# Meter.net
KiCad netlist of a schematic drawn in Altium Designer
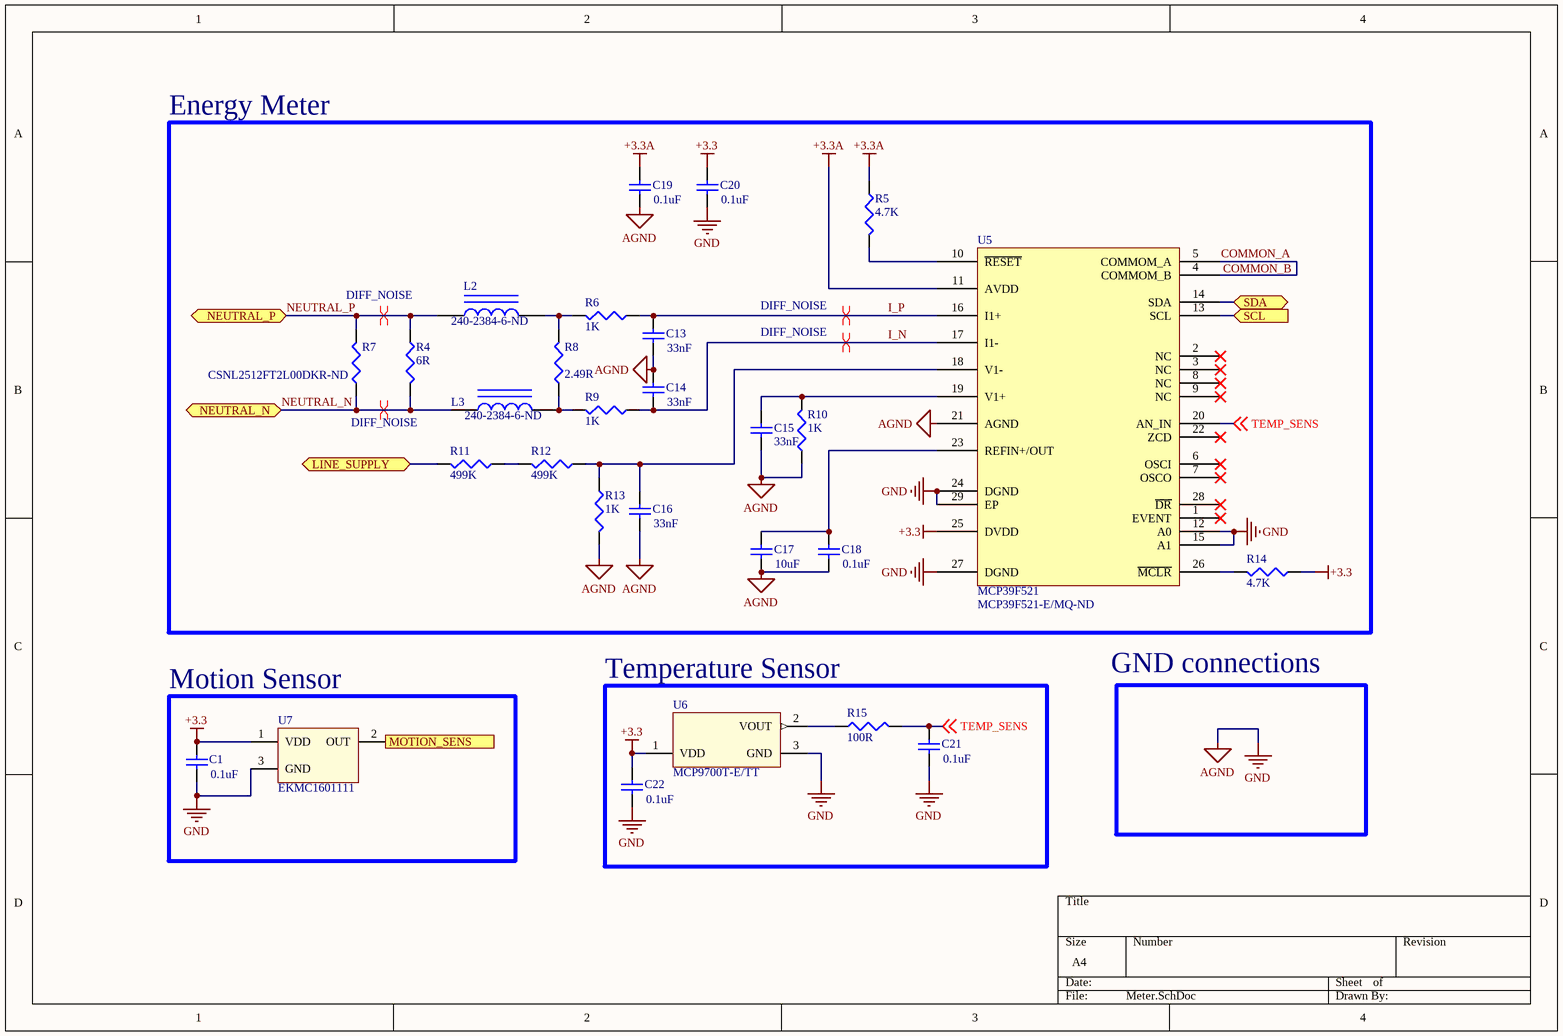
[diagram p0: Meter.SchDoc]

(export (version "E")
  (design (tool "Eeschema 10.0.6"))
  (components
    (comp (ref "C1")
      (value "0.1uF")
      (footprint "C0603")
      (description "Capacitor (Semiconductor SIM Model)")
      (fields (field (name "Comment") "MUDAR FOOTPRINT") (field (name "PUBLISHER") "Altium Limited"))
      (libsource (lib "Miscellaneous Devices") (part "Cap Semi"))
    )
    (comp (ref "C13")
      (value "33nF")
      (footprint "C0603")
      (description "Capacitor (Semiconductor SIM Model)")
      (fields (field (name "Comment") "MUDAR FOOTPRINT") (field (name "PUBLISHER") "Altium Limited"))
      (libsource (lib "Miscellaneous Devices") (part "Cap Semi"))
    )
    (comp (ref "C14")
      (value "33nF")
      (footprint "C0603")
      (description "Capacitor (Semiconductor SIM Model)")
      (fields (field (name "Comment") "MUDAR FOOTPRINT") (field (name "PUBLISHER") "Altium Limited"))
      (libsource (lib "Miscellaneous Devices") (part "Cap Semi"))
    )
    (comp (ref "C15")
      (value "33nF")
      (footprint "C0603")
      (description "Capacitor (Semiconductor SIM Model)")
      (fields (field (name "Comment") "MUDAR FOOTPRINT") (field (name "PUBLISHER") "Altium Limited"))
      (libsource (lib "Miscellaneous Devices") (part "Cap Semi"))
    )
    (comp (ref "C16")
      (value "33nF")
      (footprint "C0603")
      (description "Capacitor (Semiconductor SIM Model)")
      (fields (field (name "Comment") "MUDAR FOOTPRINT") (field (name "PUBLISHER") "Altium Limited"))
      (libsource (lib "Miscellaneous Devices") (part "Cap Semi"))
    )
    (comp (ref "C17")
      (value "10uF")
      (footprint "C0805")
      (description "Capacitor (Semiconductor SIM Model)")
      (fields (field (name "Comment") "MUDAR FOOTPRINT") (field (name "PUBLISHER") "Altium Limited"))
      (libsource (lib "Miscellaneous Devices") (part "Cap Semi"))
    )
    (comp (ref "C18")
      (value "0.1uF")
      (footprint "C0603")
      (description "Capacitor (Semiconductor SIM Model)")
      (fields (field (name "Comment") "MUDAR FOOTPRINT") (field (name "PUBLISHER") "Altium Limited"))
      (libsource (lib "Miscellaneous Devices") (part "Cap Semi"))
    )
    (comp (ref "C19")
      (value "0.1uF")
      (footprint "C0603")
      (description "Capacitor (Semiconductor SIM Model)")
      (fields (field (name "Comment") "MUDAR FOOTPRINT") (field (name "PUBLISHER") "Altium Limited"))
      (libsource (lib "Miscellaneous Devices") (part "Cap Semi"))
    )
    (comp (ref "C20")
      (value "0.1uF")
      (footprint "C0603")
      (description "Capacitor (Semiconductor SIM Model)")
      (fields (field (name "Comment") "MUDAR FOOTPRINT") (field (name "PUBLISHER") "Altium Limited"))
      (libsource (lib "Miscellaneous Devices") (part "Cap Semi"))
    )
    (comp (ref "C21")
      (value "0.1uF")
      (footprint "C0603")
      (description "Capacitor (Semiconductor SIM Model)")
      (fields (field (name "Comment") "MUDAR FOOTPRINT") (field (name "PUBLISHER") "Altium Limited"))
      (libsource (lib "Miscellaneous Devices") (part "Cap Semi"))
    )
    (comp (ref "C22")
      (value "0.1uF")
      (footprint "C0603")
      (description "Capacitor (Semiconductor SIM Model)")
      (fields (field (name "Comment") "MUDAR FOOTPRINT") (field (name "PUBLISHER") "Altium Limited"))
      (libsource (lib "Miscellaneous Devices") (part "Cap Semi"))
    )
    (comp (ref "L2")
      (value "FERRITE BEAD")
      (footprint "6-0805_N")
      (description "Magnetic-Core Inductor")
      (fields
        (field (name "SUPPLIER PART NUMBER 1") "240-2384-6-ND")
        (field (name "PUBLISHER") "Altium Limited")
      )
      (libsource (lib "Miscellaneous Devices") (part "Inductor Iron"))
    )
    (comp (ref "L3")
      (value "FERRITE BEAD")
      (footprint "6-0805_N")
      (description "Magnetic-Core Inductor")
      (fields
        (field (name "SUPPLIER PART NUMBER 1") "240-2384-6-ND")
        (field (name "PUBLISHER") "Altium Limited")
      )
      (libsource (lib "Miscellaneous Devices") (part "Inductor Iron"))
    )
    (comp (ref "R4")
      (value "6R")
      (footprint "R0603")
      (description "Resistor")
      (fields (field (name "Comment") "Res3") (field (name "PUBLISHER") "Altium Limited"))
      (libsource (lib "Miscellaneous Devices") (part "Res3"))
    )
    (comp (ref "R5")
      (value "4.7K")
      (footprint "R0603")
      (description "Resistor")
      (fields (field (name "Comment") "Res3") (field (name "PUBLISHER") "Altium Limited"))
      (libsource (lib "Miscellaneous Devices") (part "Res3"))
    )
    (comp (ref "R6")
      (value "1K")
      (footprint "R0603")
      (description "Resistor")
      (fields (field (name "Comment") "Res3") (field (name "PUBLISHER") "Altium Limited"))
      (libsource (lib "Miscellaneous Devices") (part "Res3"))
    )
    (comp (ref "R7")
      (value "SHUNT")
      (footprint "RES2512")
      (description "Resistor")
      (fields
        (field (name "SUPPLIER PART NUMBER 1") "CSNL2512FT2L00DKR-ND")
        (field (name "PUBLISHER") "Altium Limited")
      )
      (libsource (lib "Miscellaneous Devices") (part "Res3"))
    )
    (comp (ref "R8")
      (value "2.49R")
      (footprint "R0603")
      (description "Resistor")
      (fields (field (name "Comment") "Res3") (field (name "PUBLISHER") "Altium Limited"))
      (libsource (lib "Miscellaneous Devices") (part "Res3"))
    )
    (comp (ref "R9")
      (value "1K")
      (footprint "R0603")
      (description "Resistor")
      (fields (field (name "Comment") "Res3") (field (name "PUBLISHER") "Altium Limited"))
      (libsource (lib "Miscellaneous Devices") (part "Res3"))
    )
    (comp (ref "R10")
      (value "1K")
      (footprint "R0603")
      (description "Resistor")
      (fields (field (name "Comment") "Res3") (field (name "PUBLISHER") "Altium Limited"))
      (libsource (lib "Miscellaneous Devices") (part "Res3"))
    )
    (comp (ref "R11")
      (value "499K")
      (footprint "12Z-2010")
      (description "Resistor")
      (fields (field (name "Comment") "Res3") (field (name "PUBLISHER") "Altium Limited"))
      (libsource (lib "Miscellaneous Devices") (part "Res3"))
    )
    (comp (ref "R12")
      (value "499K")
      (footprint "12Z-2010")
      (description "Resistor")
      (fields (field (name "Comment") "Res3") (field (name "PUBLISHER") "Altium Limited"))
      (libsource (lib "Miscellaneous Devices") (part "Res3"))
    )
    (comp (ref "R13")
      (value "1K")
      (footprint "R0603")
      (description "Resistor")
      (fields (field (name "Comment") "Res3") (field (name "PUBLISHER") "Altium Limited"))
      (libsource (lib "Miscellaneous Devices") (part "Res3"))
    )
    (comp (ref "R14")
      (value "4.7K")
      (footprint "R0603")
      (description "Resistor")
      (fields (field (name "Comment") "Res3") (field (name "PUBLISHER") "Altium Limited"))
      (libsource (lib "Miscellaneous Devices") (part "Res3"))
    )
    (comp (ref "R15")
      (value "100R")
      (footprint "R0603")
      (description "Resistor")
      (fields (field (name "Comment") "Res3") (field (name "PUBLISHER") "Altium Limited"))
      (libsource (lib "Miscellaneous Devices") (part "Res3"))
    )
    (comp (ref "U5")
      (value "MCP39F521")
      (footprint "MCP39F521")
      (fields (field (name "SUPPLIER PART NUMBER 1") "MCP39F521-E/MQ-ND"))
      (libsource (lib "PowerMonitoring") (part "MCP39F521"))
    )
    (comp (ref "U6")
      (value "MCP9700T-E/TT")
      (footprint "SOT-233")
      (description "MCP9700 Series 5 V -40 to +125Â°C Low-Power Linear Active Thermistor")
      (fields (field (name "MF") "Microchip"))
      (libsource (lib "PowerMonitoring") (part "MCP9700T-E/TT"))
    )
    (comp (ref "U7")
      (value "EKMC1601111")
      (footprint "EKMC1601111")
      (description "Board Mount Motion & Position Sensors Digital 170uA 5m White")
      (fields (field (name "RS PART NUMBER") "1357095"))
      (libsource (lib "PowerMonitoring") (part "EKMC1601111"))
    )
  )
  (nets
    (net (code "1") (name "+3.3") (class "Default")
      (node (ref "C1") (pin "2") (pinfunction "2_2") (pintype "passive"))
      (node (ref "C20") (pin "2") (pinfunction "2_2") (pintype "passive"))
      (node (ref "C22") (pin "2") (pinfunction "2_2") (pintype "passive"))
      (node (ref "R14") (pin "2") (pinfunction "2_2") (pintype "passive"))
      (node (ref "U5") (pin "25") (pinfunction "DVDD_25") (pintype "passive"))
      (node (ref "U6") (pin "1") (pinfunction "VDD_1") (pintype "power_in"))
      (node (ref "U7") (pin "1") (pinfunction "VDD_1") (pintype "passive"))
    )
    (net (code "2") (name "+3.3A") (class "Default")
      (node (ref "C19") (pin "2") (pinfunction "2_2") (pintype "passive"))
      (node (ref "R5") (pin "1") (pinfunction "1_1") (pintype "passive"))
      (node (ref "U5") (pin "11") (pinfunction "AVDD_11") (pintype "passive"))
    )
    (net (code "3") (name "/COMMON_A") (class "Default")
      (node (ref "U5") (pin "4") (pinfunction "COMMOM_B_4") (pintype "passive"))
      (node (ref "U5") (pin "5") (pinfunction "COMMOM_A_5") (pintype "passive"))
    )
    (net (code "5") (name "/I_N") (class "Default")
      (node (ref "C14") (pin "1") (pinfunction "1_1") (pintype "passive"))
      (node (ref "R9") (pin "1") (pinfunction "1_1") (pintype "passive"))
      (node (ref "U5") (pin "17") (pinfunction "I1-_17") (pintype "passive"))
    )
    (net (code "6") (name "/I_P") (class "Default")
      (node (ref "C13") (pin "2") (pinfunction "2_2") (pintype "passive"))
      (node (ref "R6") (pin "1") (pinfunction "1_1") (pintype "passive"))
      (node (ref "U5") (pin "16") (pinfunction "I1+_16") (pintype "passive"))
    )
    (net (code "7") (name "/LINE_SUPPLY") (class "Default")
      (node (ref "R11") (pin "2") (pinfunction "2_2") (pintype "passive"))
    )
    (net (code "8") (name "/MOTION_SENS") (class "Default")
      (node (ref "U7") (pin "2") (pinfunction "OUT_2") (pintype "passive"))
    )
    (net (code "9") (name "/NEUTRAL_N") (class "Default")
      (node (ref "L3") (pin "1") (pinfunction "1_1") (pintype "passive"))
      (node (ref "R4") (pin "2") (pinfunction "2_2") (pintype "passive"))
      (node (ref "R7") (pin "1") (pinfunction "1_1") (pintype "passive"))
    )
    (net (code "10") (name "/NEUTRAL_P") (class "Default")
      (node (ref "L2") (pin "1") (pinfunction "1_1") (pintype "passive"))
      (node (ref "R4") (pin "1") (pinfunction "1_1") (pintype "passive"))
      (node (ref "R7") (pin "2") (pinfunction "2_2") (pintype "passive"))
    )
    (net (code "11") (name "/SCL") (class "Default")
      (node (ref "U5") (pin "13") (pinfunction "SCL_13") (pintype "passive"))
    )
    (net (code "12") (name "/SDA") (class "Default")
      (node (ref "U5") (pin "14") (pinfunction "SDA_14") (pintype "passive"))
    )
    (net (code "13") (name "AGND") (class "Default")
      (node (ref "C1") (pin "1") (pinfunction "1_1") (pintype "passive"))
      (node (ref "C13") (pin "1") (pinfunction "1_1") (pintype "passive"))
      (node (ref "C14") (pin "2") (pinfunction "2_2") (pintype "passive"))
      (node (ref "C15") (pin "1") (pinfunction "1_1") (pintype "passive"))
      (node (ref "C16") (pin "1") (pinfunction "1_1") (pintype "passive"))
      (node (ref "C17") (pin "1") (pinfunction "1_1") (pintype "passive"))
      (node (ref "C18") (pin "1") (pinfunction "1_1") (pintype "passive"))
      (node (ref "C19") (pin "1") (pinfunction "1_1") (pintype "passive"))
      (node (ref "C20") (pin "1") (pinfunction "1_1") (pintype "passive"))
      (node (ref "C21") (pin "1") (pinfunction "1_1") (pintype "passive"))
      (node (ref "C22") (pin "1") (pinfunction "1_1") (pintype "passive"))
      (node (ref "R10") (pin "2") (pinfunction "2_2") (pintype "passive"))
      (node (ref "R13") (pin "2") (pinfunction "2_2") (pintype "passive"))
      (node (ref "U5") (pin "12") (pinfunction "A0_12") (pintype "passive"))
      (node (ref "U5") (pin "15") (pinfunction "A1_15") (pintype "passive"))
      (node (ref "U5") (pin "21") (pinfunction "AGND_21") (pintype "passive"))
      (node (ref "U5") (pin "24") (pinfunction "DGND_24") (pintype "passive"))
      (node (ref "U5") (pin "27") (pinfunction "DGND_27") (pintype "passive"))
      (node (ref "U5") (pin "29") (pinfunction "EP_29") (pintype "passive"))
      (node (ref "U6") (pin "3") (pinfunction "GND_3") (pintype "power_in"))
      (node (ref "U7") (pin "3") (pinfunction "GND_3") (pintype "passive"))
    )
    (net (code "14") (name "Net-(L2-Pad2)") (class "Default")
      (node (ref "L2") (pin "2") (pinfunction "2_2") (pintype "passive"))
      (node (ref "R6") (pin "2") (pinfunction "2_2") (pintype "passive"))
      (node (ref "R8") (pin "2") (pinfunction "2_2") (pintype "passive"))
    )
    (net (code "15") (name "Net-(L3-Pad2)") (class "Default")
      (node (ref "L3") (pin "2") (pinfunction "2_2") (pintype "passive"))
      (node (ref "R8") (pin "1") (pinfunction "1_1") (pintype "passive"))
      (node (ref "R9") (pin "2") (pinfunction "2_2") (pintype "passive"))
    )
    (net (code "16") (name "Net-(R11-Pad1)") (class "Default")
      (node (ref "R11") (pin "1") (pinfunction "1_1") (pintype "passive"))
      (node (ref "R12") (pin "2") (pinfunction "2_2") (pintype "passive"))
    )
    (net (code "17") (name "Net-(U5-REFIN+{slash}OUT)") (class "Default")
      (node (ref "C17") (pin "2") (pinfunction "2_2") (pintype "passive"))
      (node (ref "C18") (pin "2") (pinfunction "2_2") (pintype "passive"))
      (node (ref "U5") (pin "23") (pinfunction "REFIN+/OUT_23") (pintype "passive"))
    )
    (net (code "18") (name "Net-(U5-V1+)") (class "Default")
      (node (ref "C15") (pin "2") (pinfunction "2_2") (pintype "passive"))
      (node (ref "R10") (pin "1") (pinfunction "1_1") (pintype "passive"))
      (node (ref "U5") (pin "19") (pinfunction "V1+_19") (pintype "passive"))
    )
    (net (code "19") (name "Net-(U5-V1-)") (class "Default")
      (node (ref "C16") (pin "2") (pinfunction "2_2") (pintype "passive"))
      (node (ref "R12") (pin "1") (pinfunction "1_1") (pintype "passive"))
      (node (ref "R13") (pin "1") (pinfunction "1_1") (pintype "passive"))
      (node (ref "U5") (pin "18") (pinfunction "V1-_18") (pintype "passive"))
    )
    (net (code "20") (name "Net-(U5-~{MCLR})") (class "Default")
      (node (ref "R14") (pin "1") (pinfunction "1_1") (pintype "passive"))
      (node (ref "U5") (pin "26") (pinfunction "~{MCLR}_26") (pintype "passive"))
    )
    (net (code "21") (name "Net-(U5-~{RESET})") (class "Default")
      (node (ref "R5") (pin "2") (pinfunction "2_2") (pintype "passive"))
      (node (ref "U5") (pin "10") (pinfunction "~{RESET}_10") (pintype "passive"))
    )
    (net (code "22") (name "Net-(U6-VOUT)") (class "Default")
      (node (ref "R15") (pin "1") (pinfunction "1_1") (pintype "passive"))
      (node (ref "U6") (pin "2") (pinfunction "VOUT_2") (pintype "output"))
    )
    (net (code "23") (name "TEMP_SENS") (class "Default")
      (node (ref "C21") (pin "2") (pinfunction "2_2") (pintype "passive"))
      (node (ref "R15") (pin "2") (pinfunction "2_2") (pintype "passive"))
      (node (ref "U5") (pin "20") (pinfunction "AN_IN_20") (pintype "passive"))
    )
    (net (code "24") (name "unconnected-(U5-EVENT-Pad1)") (class "Default")
      (node (ref "U5") (pin "1") (pinfunction "EVENT_1") (pintype "passive+no_connect"))
    )
    (net (code "25") (name "unconnected-(U5-NC-Pad2)") (class "Default")
      (node (ref "U5") (pin "2") (pinfunction "NC_2") (pintype "passive+no_connect"))
    )
    (net (code "26") (name "unconnected-(U5-NC-Pad3)") (class "Default")
      (node (ref "U5") (pin "3") (pinfunction "NC_3") (pintype "passive+no_connect"))
    )
    (net (code "27") (name "unconnected-(U5-NC-Pad8)") (class "Default")
      (node (ref "U5") (pin "8") (pinfunction "NC_8") (pintype "passive+no_connect"))
    )
    (net (code "28") (name "unconnected-(U5-NC-Pad9)") (class "Default")
      (node (ref "U5") (pin "9") (pinfunction "NC_9") (pintype "passive+no_connect"))
    )
    (net (code "29") (name "unconnected-(U5-OSCI-Pad6)") (class "Default")
      (node (ref "U5") (pin "6") (pinfunction "OSCI_6") (pintype "passive+no_connect"))
    )
    (net (code "30") (name "unconnected-(U5-OSCO-Pad7)") (class "Default")
      (node (ref "U5") (pin "7") (pinfunction "OSCO_7") (pintype "passive+no_connect"))
    )
    (net (code "31") (name "unconnected-(U5-ZCD-Pad22)") (class "Default")
      (node (ref "U5") (pin "22") (pinfunction "ZCD_22") (pintype "passive+no_connect"))
    )
    (net (code "32") (name "unconnected-(U5-~{DR}-Pad28)") (class "Default")
      (node (ref "U5") (pin "28") (pinfunction "~{DR}_28") (pintype "passive+no_connect"))
    )
  )
)
